# Filter.net
KiCad netlist of a schematic drawn in Altium Designer
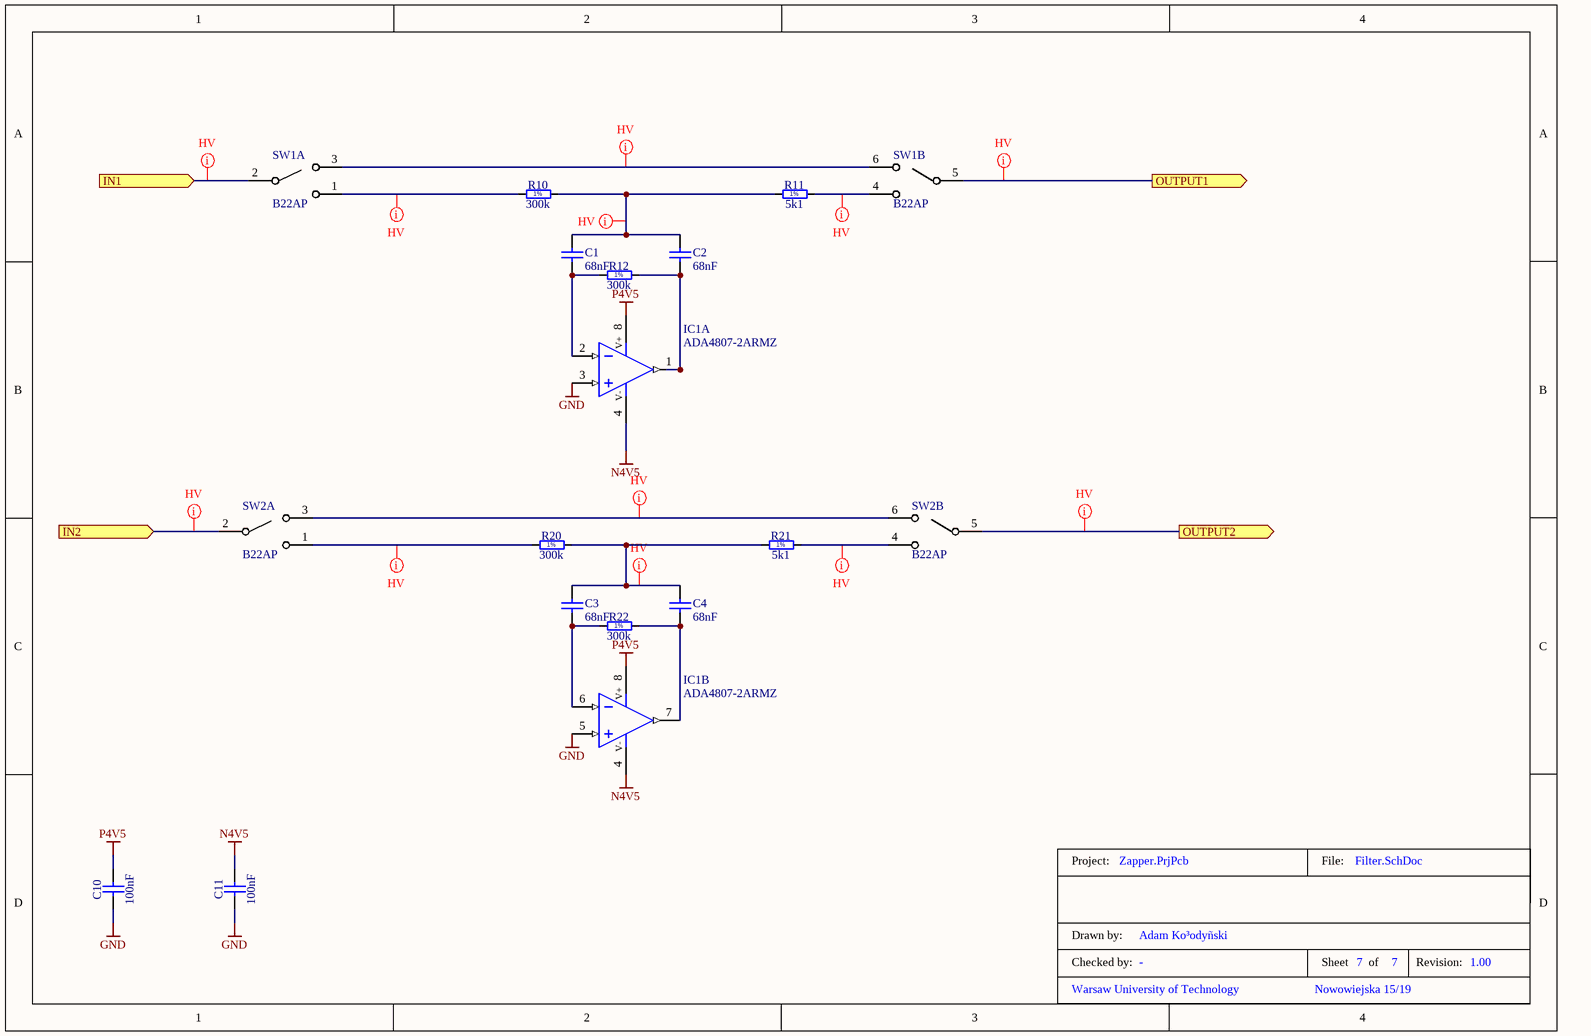
[diagram p0: Filter.SchDoc]

(export (version "E")
  (design (tool "Eeschema 10.0.6"))
  (components
    (comp (ref "C1")
      (value "68nF")
      (footprint "CAPC2012X125 - HV")
      (description "CAP CER 68nF 250V X7R 10% Pad SMD 0805 125C Automotive T/R")
      (fields (field (name "TOLERANCE") "10%"))
      (libsource (lib "CapacitorLibrary") (part "C0805C683KARACAUTO"))
    )
    (comp (ref "C2")
      (value "68nF")
      (footprint "CAPC2012X125 - HV")
      (description "CAP CER 68nF 250V X7R 10% Pad SMD 0805 125C Automotive T/R")
      (fields (field (name "TOLERANCE") "10%"))
      (libsource (lib "CapacitorLibrary") (part "C0805C683KARACAUTO"))
    )
    (comp (ref "C3")
      (value "68nF")
      (footprint "CAPC2012X125 - HV")
      (description "CAP CER 68nF 250V X7R 10% Pad SMD 0805 125C Automotive T/R")
      (fields (field (name "TOLERANCE") "10%"))
      (libsource (lib "CapacitorLibrary") (part "C0805C683KARACAUTO"))
    )
    (comp (ref "C4")
      (value "68nF")
      (footprint "CAPC2012X125 - HV")
      (description "CAP CER 68nF 250V X7R 10% Pad SMD 0805 125C Automotive T/R")
      (fields (field (name "TOLERANCE") "10%"))
      (libsource (lib "CapacitorLibrary") (part "C0805C683KARACAUTO"))
    )
    (comp (ref "C10")
      (value "100nF")
      (footprint "CAPC1005X55N")
      (description "Non-polarised capacitor")
      (fields
        (field (name "PART NUMBER") "CC0402_100NF_16V_10%_X7R")
        (field (name "VOLTAGE") "16V")
        (field (name "AUTHOR") "CERN DEM JLC")
      )
      (libsource (lib "Capacitors") (part "Capacitor - non polarized"))
    )
    (comp (ref "C11")
      (value "100nF")
      (footprint "CAPC1005X55N")
      (description "Non-polarised capacitor")
      (fields
        (field (name "PART NUMBER") "CC0402_100NF_16V_10%_X7R")
        (field (name "VOLTAGE") "16V")
        (field (name "AUTHOR") "CERN DEM JLC")
      )
      (libsource (lib "Capacitors") (part "Capacitor - non polarized"))
    )
    (comp (ref "IC1")
      (value "ADA4807-2ARMZ")
      (footprint "SOP65P490X110-8N")
      (description "Operational Amplifier, 180 Mhz, 2, 225 V/ S, 2.7V To 11V, Msop, 8")
      (libsource (lib "InzLib") (part "ADA4807-2ARMZ"))
    )
    (comp (ref "R10")
      (value "300k")
      (footprint "RESC2012X60N")
      (description "Resistor - 1%")
      (fields
        (field (name "PART NUMBER") "R0805_300K_1%_0.125W_100PPM")
        (field (name "POWER") "0.125W")
        (field (name "AUTHOR") "CERN DEM JLC")
      )
      (libsource (lib "Resistors") (part "Resistor - 1%"))
    )
    (comp (ref "R11")
      (value "5k1")
      (footprint "RESC1608X55N")
      (description "Resistor - 1%")
      (fields
        (field (name "PART NUMBER") "R0603_5K1_1%_0.1W_100PPM")
        (field (name "POWER") "0.1W")
        (field (name "AUTHOR") "CERN DEM JLC")
      )
      (libsource (lib "Resistors") (part "Resistor - 1%"))
    )
    (comp (ref "R12")
      (value "300k")
      (footprint "RESC2012X60N")
      (description "Resistor - 1%")
      (fields
        (field (name "PART NUMBER") "R0805_300K_1%_0.125W_100PPM")
        (field (name "POWER") "0.125W")
        (field (name "AUTHOR") "CERN DEM JLC")
      )
      (libsource (lib "Resistors") (part "Resistor - 1%"))
    )
    (comp (ref "R20")
      (value "300k")
      (footprint "RESC2012X60N")
      (description "Resistor - 1%")
      (fields
        (field (name "PART NUMBER") "R0805_300K_1%_0.125W_100PPM")
        (field (name "POWER") "0.125W")
        (field (name "AUTHOR") "CERN DEM JLC")
      )
      (libsource (lib "Resistors") (part "Resistor - 1%"))
    )
    (comp (ref "R21")
      (value "5k1")
      (footprint "RESC1608X55N")
      (description "Resistor - 1%")
      (fields
        (field (name "PART NUMBER") "R0603_5K1_1%_0.1W_100PPM")
        (field (name "POWER") "0.1W")
        (field (name "AUTHOR") "CERN DEM JLC")
      )
      (libsource (lib "Resistors") (part "Resistor - 1%"))
    )
    (comp (ref "R22")
      (value "300k")
      (footprint "RESC2012X60N")
      (description "Resistor - 1%")
      (fields
        (field (name "PART NUMBER") "R0805_300K_1%_0.125W_100PPM")
        (field (name "POWER") "0.125W")
        (field (name "AUTHOR") "CERN DEM JLC")
      )
      (libsource (lib "Resistors") (part "Resistor - 1%"))
    )
    (comp (ref "SW1")
      (value "B22AP")
      (footprint "B22AP")
      (description "NKK SWITCHES         B22AP            SWITCH, TOGGLE, DPDT, 0.1A, 28VAC")
      (libsource (lib "") (part "B22AP_1"))
    )
    (comp (ref "SW2")
      (value "B22AP")
      (footprint "B22AP")
      (description "NKK SWITCHES         B22AP            SWITCH, TOGGLE, DPDT, 0.1A, 28VAC")
      (libsource (lib "InzLib") (part "B22AP"))
    )
    (comp (ref "TitleBlock7") (value "TitleBlock") (libsource (lib "InzLib") (part "TitleBlock")))
  )
  (nets
    (net (code "1") (name "/IN1") (class "Default")
      (node (ref "SW1") (pin "2") (pinfunction "COM_2") (pintype "passive"))
    )
    (net (code "2") (name "/IN2") (class "Default")
      (node (ref "SW2") (pin "2") (pinfunction "COM_2") (pintype "passive"))
    )
    (net (code "3") (name "/OUTPUT1") (class "Default")
      (node (ref "SW1") (pin "5") (pinfunction "COM_5") (pintype "passive"))
    )
    (net (code "4") (name "/OUTPUT2") (class "Default")
      (node (ref "SW2") (pin "5") (pinfunction "COM_5") (pintype "passive"))
    )
    (net (code "5") (name "GND") (class "Default")
      (node (ref "C10") (pin "1") (pinfunction "1_1") (pintype "passive"))
      (node (ref "C11") (pin "1") (pinfunction "1_1") (pintype "passive"))
      (node (ref "IC1") (pin "3") (pinfunction "IN+_3") (pintype "input"))
      (node (ref "IC1") (pin "5") (pinfunction "IN+_5") (pintype "input"))
    )
    (net (code "6") (name "N4V5") (class "Default")
      (node (ref "C11") (pin "2") (pinfunction "2_2") (pintype "passive"))
      (node (ref "IC1") (pin "4") (pinfunction "V-_4") (pintype "power_in"))
    )
    (net (code "7") (name "Net-(C1-Pad2)") (class "Default")
      (node (ref "C1") (pin "2") (pinfunction "2_2") (pintype "passive"))
      (node (ref "C2") (pin "2") (pinfunction "2_2") (pintype "passive"))
      (node (ref "R10") (pin "2") (pinfunction "2_2") (pintype "passive"))
      (node (ref "R11") (pin "1") (pinfunction "1_1") (pintype "passive"))
    )
    (net (code "8") (name "Net-(C3-Pad2)") (class "Default")
      (node (ref "C3") (pin "2") (pinfunction "2_2") (pintype "passive"))
      (node (ref "C4") (pin "2") (pinfunction "2_2") (pintype "passive"))
      (node (ref "R20") (pin "2") (pinfunction "2_2") (pintype "passive"))
      (node (ref "R21") (pin "1") (pinfunction "1_1") (pintype "passive"))
    )
    (net (code "9") (name "Net-(IC1A-IN-)") (class "Default")
      (node (ref "C1") (pin "1") (pinfunction "1_1") (pintype "passive"))
      (node (ref "IC1") (pin "2") (pinfunction "IN-_2") (pintype "input"))
      (node (ref "R12") (pin "1") (pinfunction "1_1") (pintype "passive"))
    )
    (net (code "10") (name "Net-(IC1A-OUT)") (class "Default")
      (node (ref "C2") (pin "1") (pinfunction "1_1") (pintype "passive"))
      (node (ref "IC1") (pin "1") (pinfunction "OUT_1") (pintype "output"))
      (node (ref "R12") (pin "2") (pinfunction "2_2") (pintype "passive"))
    )
    (net (code "11") (name "Net-(IC1B-IN-)") (class "Default")
      (node (ref "C3") (pin "1") (pinfunction "1_1") (pintype "passive"))
      (node (ref "IC1") (pin "6") (pinfunction "IN-_6") (pintype "input"))
      (node (ref "R22") (pin "1") (pinfunction "1_1") (pintype "passive"))
    )
    (net (code "12") (name "Net-(IC1B-OUT)") (class "Default")
      (node (ref "C4") (pin "1") (pinfunction "1_1") (pintype "passive"))
      (node (ref "IC1") (pin "7") (pinfunction "OUT_7") (pintype "output"))
      (node (ref "R22") (pin "2") (pinfunction "2_2") (pintype "passive"))
    )
    (net (code "13") (name "Net-(SW1A-DOWN)") (class "Default")
      (node (ref "SW1") (pin "3") (pinfunction "DOWN_3") (pintype "passive"))
      (node (ref "SW1") (pin "6") (pinfunction "DOWN_6") (pintype "passive"))
    )
    (net (code "14") (name "Net-(SW1A-UP)") (class "Default")
      (node (ref "R10") (pin "1") (pinfunction "1_1") (pintype "passive"))
      (node (ref "SW1") (pin "1") (pinfunction "UP_1") (pintype "passive"))
    )
    (net (code "15") (name "Net-(SW1B-UP)") (class "Default")
      (node (ref "R11") (pin "2") (pinfunction "2_2") (pintype "passive"))
      (node (ref "SW1") (pin "4") (pinfunction "UP_4") (pintype "passive"))
    )
    (net (code "16") (name "Net-(SW2A-DOWN)") (class "Default")
      (node (ref "SW2") (pin "3") (pinfunction "DOWN_3") (pintype "passive"))
      (node (ref "SW2") (pin "6") (pinfunction "DOWN_6") (pintype "passive"))
    )
    (net (code "17") (name "Net-(SW2A-UP)") (class "Default")
      (node (ref "R20") (pin "1") (pinfunction "1_1") (pintype "passive"))
      (node (ref "SW2") (pin "1") (pinfunction "UP_1") (pintype "passive"))
    )
    (net (code "18") (name "Net-(SW2B-UP)") (class "Default")
      (node (ref "R21") (pin "2") (pinfunction "2_2") (pintype "passive"))
      (node (ref "SW2") (pin "4") (pinfunction "UP_4") (pintype "passive"))
    )
    (net (code "19") (name "P4V5") (class "Default")
      (node (ref "C10") (pin "2") (pinfunction "2_2") (pintype "passive"))
      (node (ref "IC1") (pin "8") (pinfunction "V+_8") (pintype "power_in"))
    )
  )
)
